# subsystem_intro_prj.net
KiCad netlist of a schematic drawn in Altium Designer
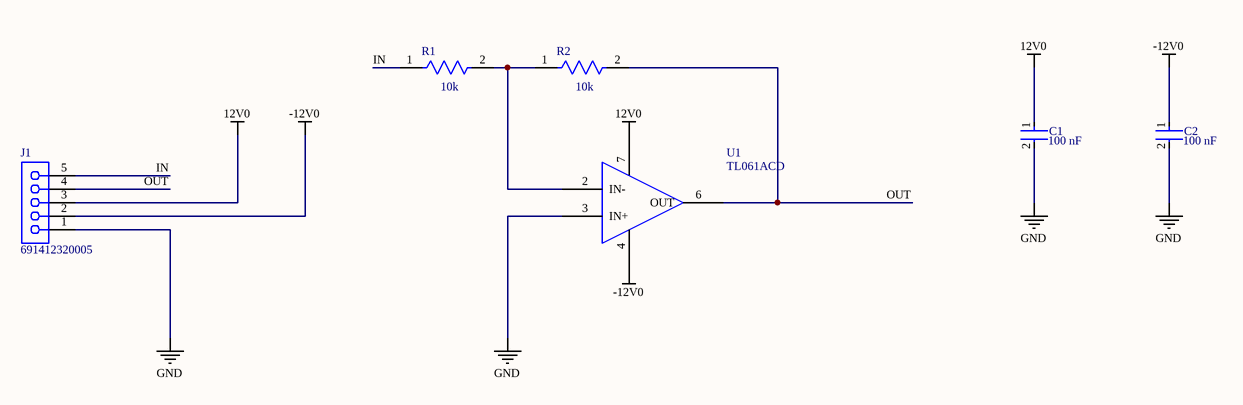
[diagram p0: subsystem_intro_prj.SchDoc]

(export (version "E")
  (design (tool "Eeschema 10.0.6"))
  (components
    (comp (ref "C1")
      (value "CC0805KRX7R9BB104")
      (footprint "FP-CC0805-0_85-MFG")
      (description "CAP CER 0.1UF 50V X7R 0805")
      (fields
        (field (name "TOLERANCE") "0.1")
        (field (name "CAPACITANCE") "100 nF")
        (field (name "MANUFACTURER") "Yageo")
      )
      (libsource (lib "Altium Content Vault") (part "11868f565c42a9108669ba33697ecf6"))
    )
    (comp (ref "C2")
      (value "CC0805KRX7R9BB104")
      (footprint "FP-CC0805-0_85-MFG")
      (description "CAP CER 0.1UF 50V X7R 0805")
      (fields
        (field (name "TOLERANCE") "0.1")
        (field (name "CAPACITANCE") "100 nF")
        (field (name "MANUFACTURER") "Yageo")
      )
      (libsource (lib "Altium Content Vault") (part "11868f565c42a9108669ba33697ecf6"))
    )
    (comp (ref "J1")
      (value "691412320005")
      (footprint "691412320005")
      (libsource (lib "Altium Content Vault") (part "TBL - 1R - 05P - Female"))
    )
    (comp (ref "R1")
      (value "RR1220P-103-D")
      (footprint "FP-RR1220-IPC_A")
      (description "10kΩ ±0.5% 0.1W 1/10W Chip Resistor 0805 (2012 Metric) Thin Film")
      (fields (field (name "RESISTANCE") "10k") (field (name "TOLERANCE") "0.5%"))
      (libsource (lib "Altium Content Vault") (part "1029c3af85768c4190bb7ad29bc67b5"))
    )
    (comp (ref "R2")
      (value "RR1220P-103-D")
      (footprint "FP-RR1220-IPC_A")
      (description "10kΩ ±0.5% 0.1W 1/10W Chip Resistor 0805 (2012 Metric) Thin Film")
      (fields (field (name "RESISTANCE") "10k") (field (name "TOLERANCE") "0.5%"))
      (libsource (lib "Altium Content Vault") (part "1029c3af85768c4190bb7ad29bc67b5"))
    )
    (comp (ref "U1") (value "TL061ACD") (footprint "TL061ACD") (libsource (lib "TL061ACD") (part "TL061ACD")))
  )
  (nets
    (net (code "1") (name "-12V0") (class "Default")
      (node (ref "C2") (pin "1") (pinfunction "1_1") (pintype "passive"))
      (node (ref "J1") (pin "2") (pinfunction "2_2") (pintype "passive"))
      (node (ref "U1") (pin "4") (pinfunction "VCC-_4") (pintype "passive"))
    )
    (net (code "2") (name "/IN") (class "Default")
      (node (ref "J1") (pin "5") (pinfunction "5_5") (pintype "passive"))
      (node (ref "R1") (pin "1") (pinfunction "1_1") (pintype "passive"))
    )
    (net (code "3") (name "/OUT") (class "Default")
      (node (ref "J1") (pin "4") (pinfunction "4_4") (pintype "passive"))
      (node (ref "R2") (pin "2") (pinfunction "2_2") (pintype "passive"))
      (node (ref "U1") (pin "6") (pinfunction "OUT_6") (pintype "passive"))
    )
    (net (code "4") (name "12V0") (class "Default")
      (node (ref "C1") (pin "1") (pinfunction "1_1") (pintype "passive"))
      (node (ref "J1") (pin "3") (pinfunction "3_3") (pintype "passive"))
      (node (ref "U1") (pin "7") (pinfunction "VCC+_7") (pintype "passive"))
    )
    (net (code "5") (name "GND") (class "Default")
      (node (ref "C1") (pin "2") (pinfunction "2_2") (pintype "passive"))
      (node (ref "C2") (pin "2") (pinfunction "2_2") (pintype "passive"))
      (node (ref "J1") (pin "1") (pinfunction "1_1") (pintype "passive"))
      (node (ref "U1") (pin "3") (pinfunction "IN+_3") (pintype "passive"))
    )
    (net (code "6") (name "Net-(U1-IN-)") (class "Default")
      (node (ref "R1") (pin "2") (pinfunction "2_2") (pintype "passive"))
      (node (ref "R2") (pin "1") (pinfunction "1_1") (pintype "passive"))
      (node (ref "U1") (pin "2") (pinfunction "IN-_2") (pintype "passive"))
    )
  )
)
